# easyeda.net
KiCad netlist of a schematic drawn in EasyEDA
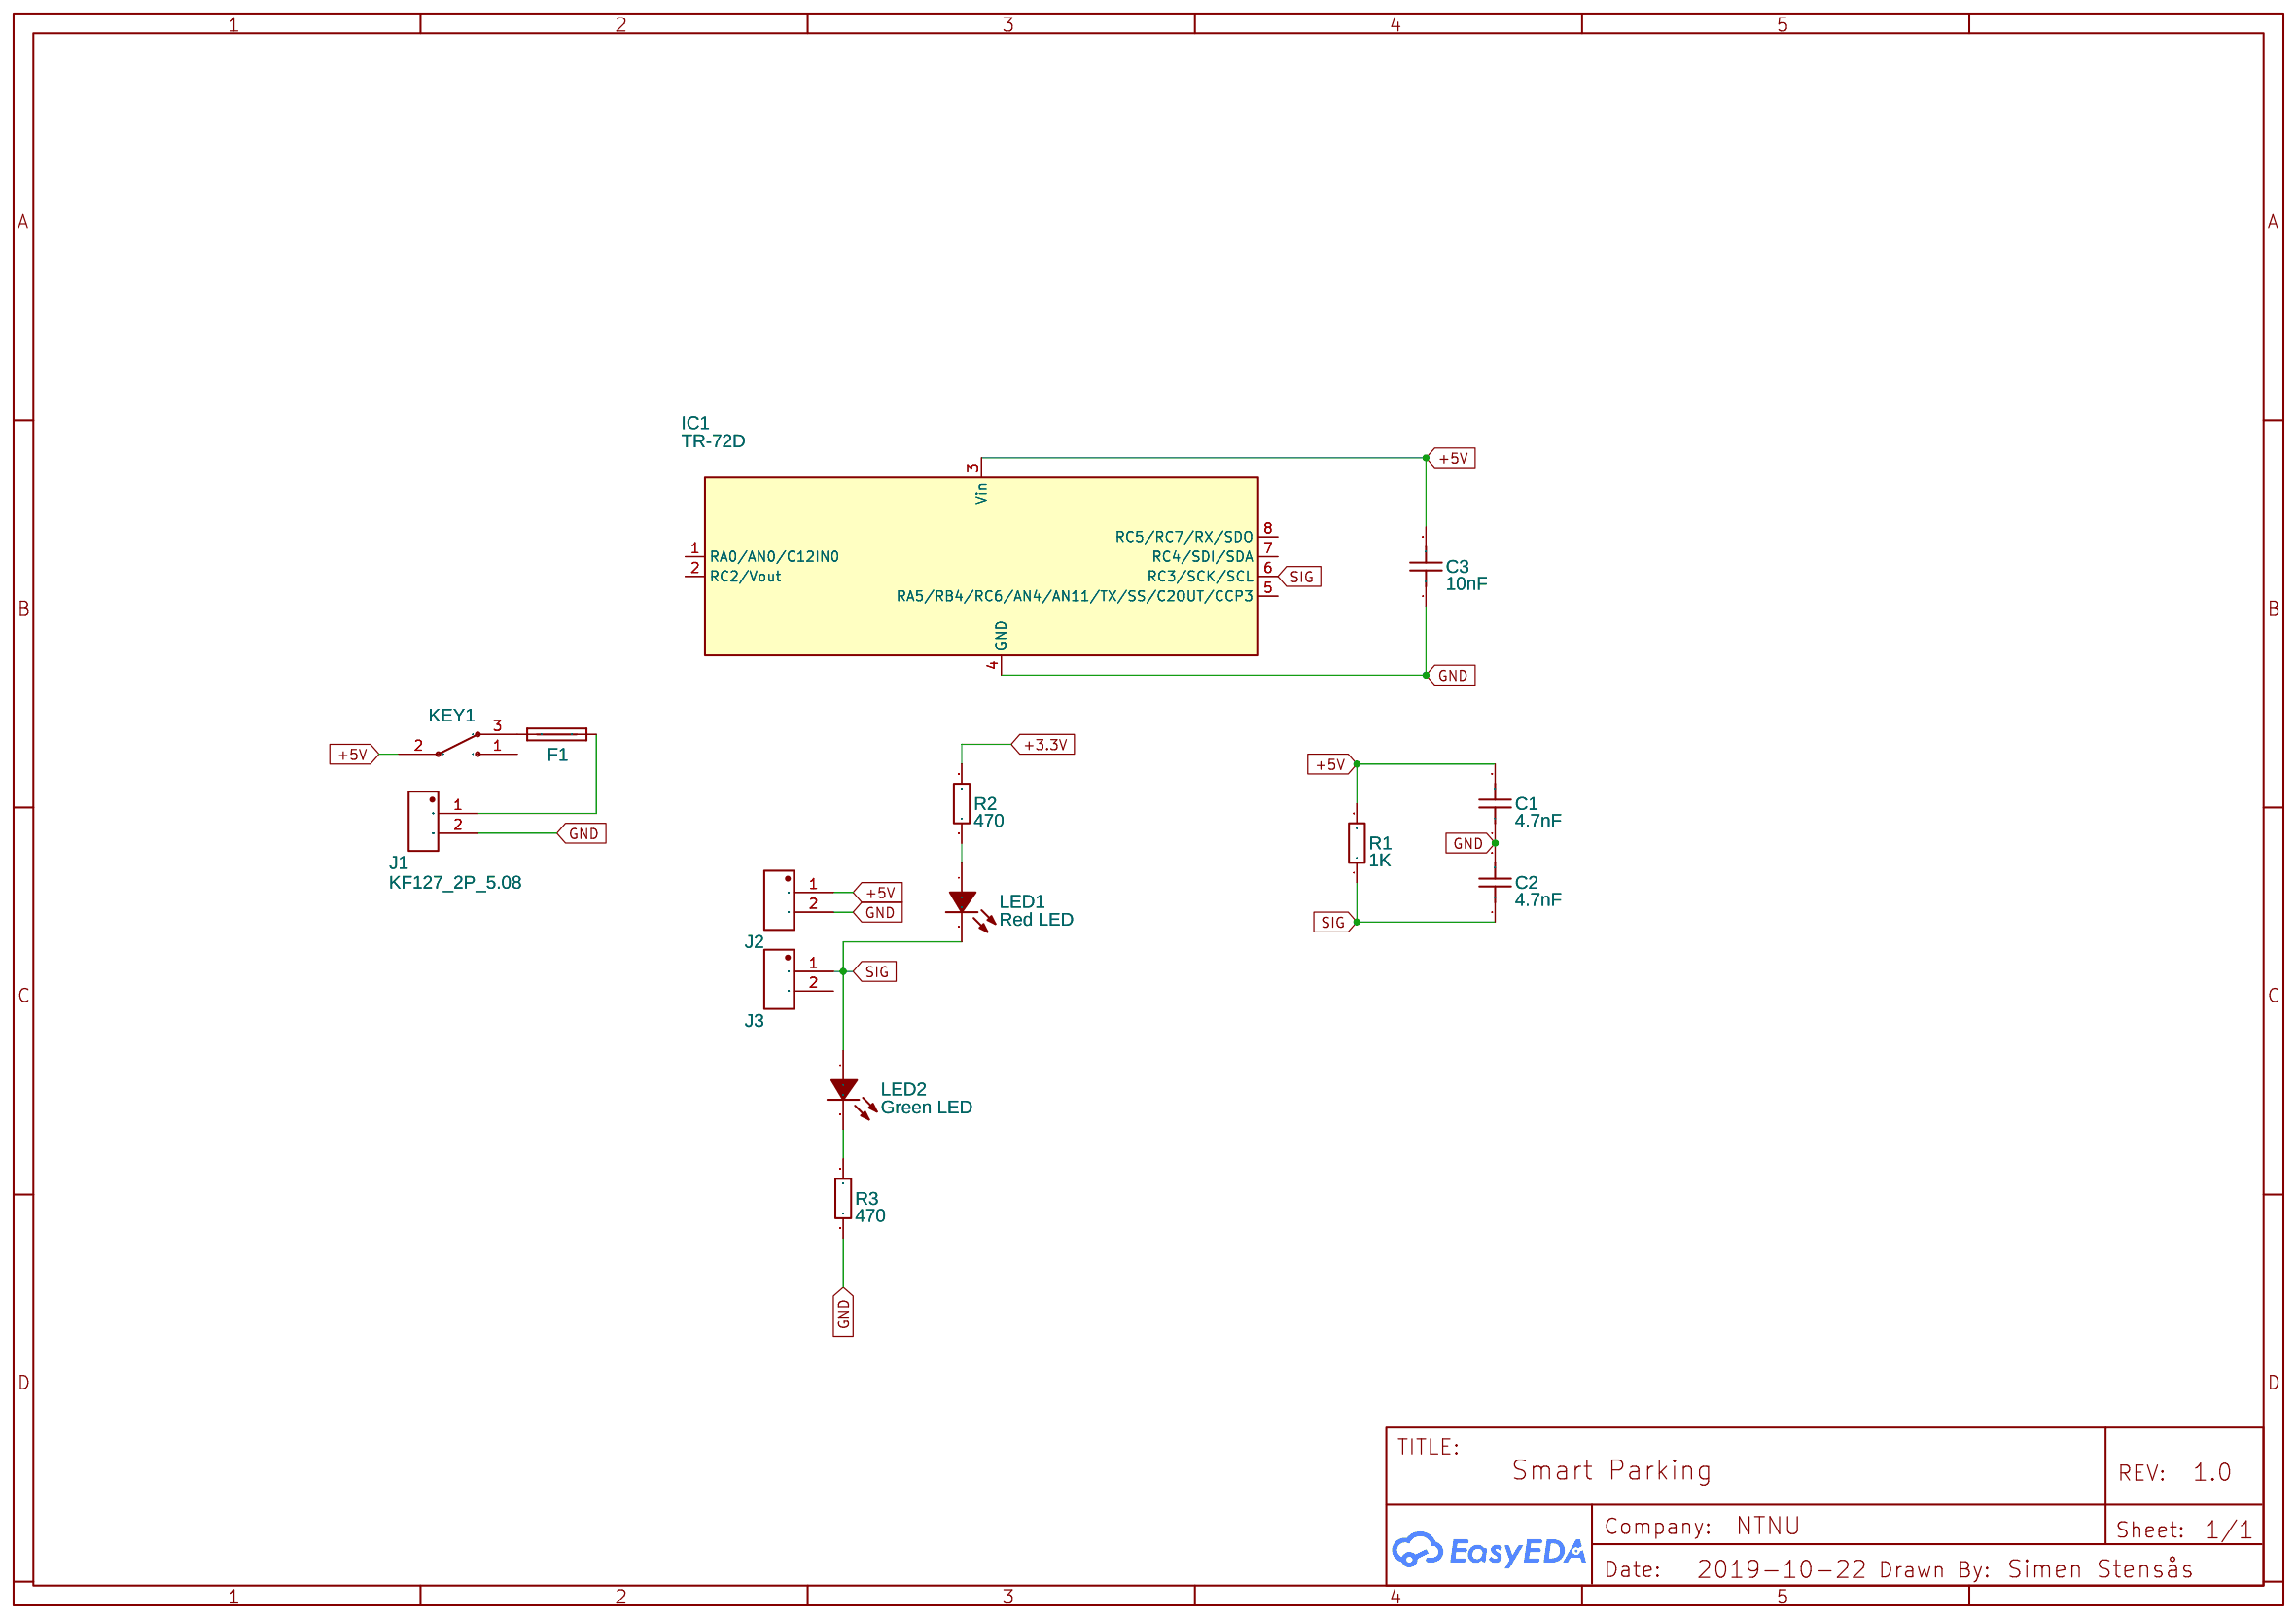
[diagram p0: Smart Parking]
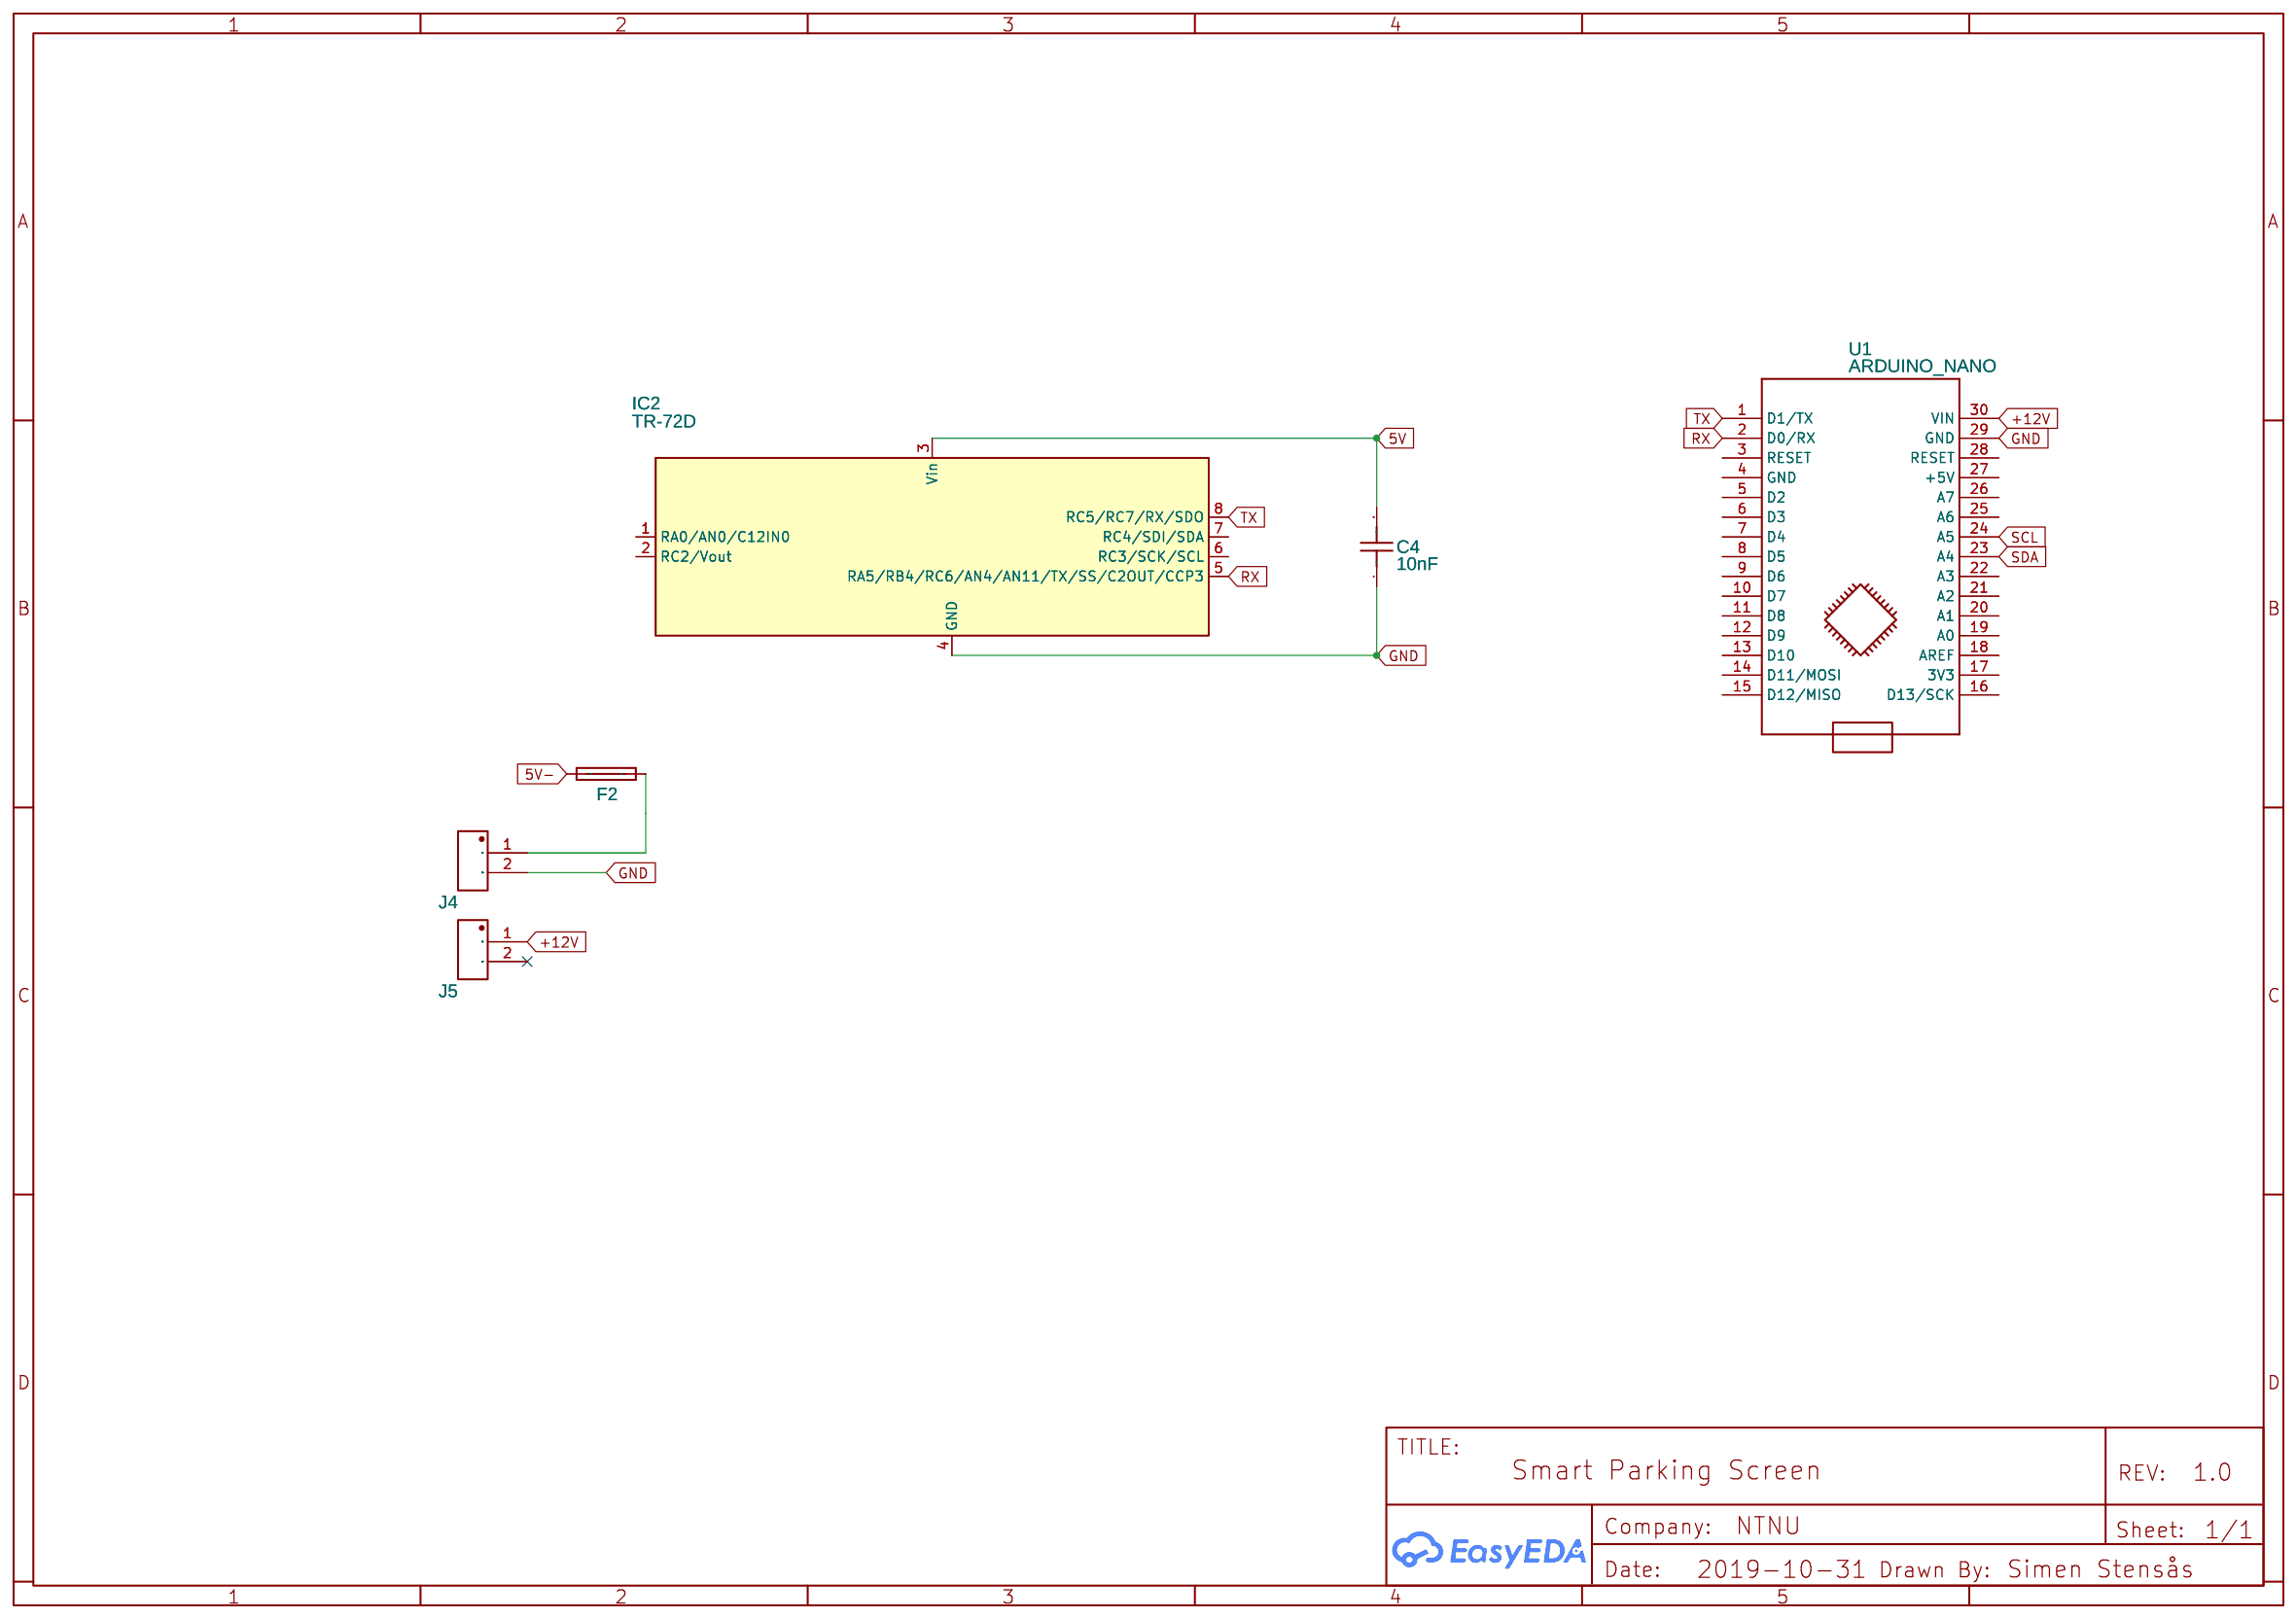
[diagram p1: Smart Parking Screen]

(export (version "E")
  (design (tool "Eeschema 10.0.6"))
  (components
    (comp (ref "C1")
      (value "4.7nF")
      (fields
        (field (name "BOM_Manufacturer Part") "0805B472K201")
        (field (name "BOM_Supplier Part") "C77474")
      )
      (libsource (lib "") (part "0805B472K201"))
    )
    (comp (ref "C2")
      (value "4.7nF")
      (fields
        (field (name "BOM_Manufacturer Part") "0805B472K201")
        (field (name "BOM_Supplier Part") "C77474")
      )
      (libsource (lib "") (part "0805B472K201"))
    )
    (comp (ref "C3")
      (value "10nF")
      (fields
        (field (name "BOM_Manufacturer Part") "0603B103K500AT")
        (field (name "BOM_Supplier Part") "C327421")
      )
      (libsource (lib "") (part "0603B103K500AT"))
    )
    (comp (ref "F1")
      (value "NO")
      (fields
        (field (name "BOM_Manufacturer Part") "3403.0015.11")
        (field (name "BOM_Supplier Part") "693-3403.0015.11")
      )
      (libsource (lib "") (part "Unknown_280_355"))
    )
    (comp (ref "IC1") (value "TR-72D") (libsource (lib "") (part "Unknown_350_275")))
    (comp (ref "J1")
      (value "KF127_2P_5.08")
      (fields (field (name "BOM_Manufacturer Part") "KF127L-5.08"))
      (libsource (lib "") (part "Unknown_220_410"))
    )
    (comp (ref "J2")
      (value "KF127_2P_5.08")
      (fields (field (name "BOM_Manufacturer Part") "KF127L-5.08"))
      (libsource (lib "") (part "Unknown_400_450"))
    )
    (comp (ref "J3")
      (value "KF127_2P_5.08")
      (fields (field (name "BOM_Manufacturer Part") "KF127L-5.08"))
      (libsource (lib "") (part "Unknown_400_490"))
    )
    (comp (ref "KEY1")
      (value "MSK-11027 Toggle Switches")
      (fields (field (name "BOM_Supplier Part") "C21381"))
      (libsource (lib "") (part "Unknown_225_365"))
    )
    (comp (ref "LED1")
      (value "Red LED")
      (fields
        (field (name "BOM_Manufacturer Part") "3528 Red LED")
        (field (name "BOM_Supplier Part") "C2305")
      )
      (libsource (lib "") (part "Unknown_485_450"))
    )
    (comp (ref "LED2")
      (value "Green LED")
      (fields
        (field (name "BOM_Manufacturer Part") "3528 Red LED")
        (field (name "BOM_Supplier Part") "C2305")
      )
      (libsource (lib "") (part "Unknown_425_545"))
    )
    (comp (ref "R1")
      (value "1K")
      (fields
        (field (name "BOM_Manufacturer Part") "CR0805J80102G")
        (field (name "BOM_Supplier Part") "C101925")
      )
      (libsource (lib "") (part "CR0805J80102G"))
    )
    (comp (ref "R2")
      (value "470")
      (fields
        (field (name "BOM_Manufacturer Part") "CR0805J80102G")
        (field (name "BOM_Supplier Part") "C101925")
      )
      (libsource (lib "") (part "CR0805J80102G"))
    )
    (comp (ref "R3")
      (value "470")
      (fields
        (field (name "BOM_Manufacturer Part") "CR0805J80102G")
        (field (name "BOM_Supplier Part") "C101925")
      )
      (libsource (lib "") (part "CR0805J80102G"))
    )
    (comp (ref "C4")
      (value "10nF")
      (fields
        (field (name "BOM_Manufacturer Part") "0603B103K500AT")
        (field (name "BOM_Supplier Part") "C327421")
      )
      (libsource (lib "") (part "0603B103K500AT"))
    )
    (comp (ref "F2")
      (value "NO")
      (fields
        (field (name "BOM_Manufacturer Part") "3403.0015.11")
        (field (name "BOM_Supplier Part") "693-3403.0015.11")
      )
      (libsource (lib "") (part "Unknown_305_375"))
    )
    (comp (ref "IC2") (value "TR-72D") (libsource (lib "") (part "Unknown_325_265")))
    (comp (ref "J4")
      (value "KF127_2P_5.08")
      (fields (field (name "BOM_Manufacturer Part") "KF127L-5.08"))
      (libsource (lib "") (part "Unknown_245_430"))
    )
    (comp (ref "J5")
      (value "KF127_2P_5.08")
      (fields (field (name "BOM_Manufacturer Part") "KF127L-5.08"))
      (libsource (lib "") (part "Unknown_245_475"))
    )
    (comp (ref "U1") (value "ARDUINO_NANO") (libsource (lib "") (part "Unknown_935_280")))
  )
  (nets
    (net (code "1") (name "+3.3V") (class "Default")
      (node (ref "R2") (pin "2") (pinfunction "2_2") (pintype "unspecified"))
    )
    (net (code "2") (name "+5V") (class "Default")
      (node (ref "C1") (pin "2") (pinfunction "2_2") (pintype "unspecified"))
      (node (ref "C3") (pin "2") (pinfunction "2_2") (pintype "unspecified"))
      (node (ref "IC1") (pin "3") (pinfunction "Vin_3") (pintype "bidirectional"))
      (node (ref "J2") (pin "1") (pinfunction "PIN1_1") (pintype "unspecified"))
      (node (ref "KEY1") (pin "2") (pinfunction "2_2") (pintype "unspecified"))
      (node (ref "R1") (pin "2") (pinfunction "2_2") (pintype "unspecified"))
    )
    (net (code "3") (name "+12V") (class "Default")
      (node (ref "J5") (pin "1") (pinfunction "PIN1_1") (pintype "unspecified"))
      (node (ref "U1") (pin "30") (pinfunction "VIN_30") (pintype "unspecified"))
    )
    (net (code "4") (name "5V") (class "Default")
      (node (ref "C4") (pin "2") (pinfunction "2_2") (pintype "unspecified"))
      (node (ref "IC2") (pin "3") (pinfunction "Vin_3") (pintype "bidirectional"))
    )
    (net (code "5") (name "5V-") (class "Default")
      (node (ref "F2") (pin "1") (pinfunction "1_1") (pintype "bidirectional"))
    )
    (net (code "6") (name "GND") (class "Default")
      (node (ref "C1") (pin "1") (pinfunction "1_1") (pintype "unspecified"))
      (node (ref "C2") (pin "2") (pinfunction "2_2") (pintype "unspecified"))
      (node (ref "C3") (pin "1") (pinfunction "1_1") (pintype "unspecified"))
      (node (ref "C4") (pin "1") (pinfunction "1_1") (pintype "unspecified"))
      (node (ref "IC1") (pin "4") (pinfunction "GND_4") (pintype "bidirectional"))
      (node (ref "IC2") (pin "4") (pinfunction "GND_4") (pintype "bidirectional"))
      (node (ref "J1") (pin "2") (pinfunction "PIN2_2") (pintype "unspecified"))
      (node (ref "J2") (pin "2") (pinfunction "PIN2_2") (pintype "unspecified"))
      (node (ref "J4") (pin "2") (pinfunction "PIN2_2") (pintype "unspecified"))
      (node (ref "R3") (pin "1") (pinfunction "1_1") (pintype "unspecified"))
      (node (ref "U1") (pin "29") (pinfunction "GND_29") (pintype "unspecified"))
    )
    (net (code "7") (name "Net-(F1-Pad1)") (class "Default")
      (node (ref "F1") (pin "1") (pinfunction "1_1") (pintype "bidirectional"))
      (node (ref "KEY1") (pin "3") (pinfunction "3_3") (pintype "unspecified"))
    )
    (net (code "8") (name "Net-(J1-PIN1)") (class "Default")
      (node (ref "F1") (pin "2") (pinfunction "2_2") (pintype "bidirectional"))
      (node (ref "J1") (pin "1") (pinfunction "PIN1_1") (pintype "unspecified"))
    )
    (net (code "9") (name "Net-(J4-PIN1)") (class "Default")
      (node (ref "F2") (pin "2") (pinfunction "2_2") (pintype "bidirectional"))
      (node (ref "J4") (pin "1") (pinfunction "PIN1_1") (pintype "unspecified"))
    )
    (net (code "10") (name "Net-(LED1-A)") (class "Default")
      (node (ref "LED1") (pin "1") (pinfunction "A_1") (pintype "unspecified"))
      (node (ref "R2") (pin "1") (pinfunction "1_1") (pintype "unspecified"))
    )
    (net (code "11") (name "Net-(LED2-K)") (class "Default")
      (node (ref "LED2") (pin "2") (pinfunction "K_2") (pintype "unspecified"))
      (node (ref "R3") (pin "2") (pinfunction "2_2") (pintype "unspecified"))
    )
    (net (code "12") (name "RX") (class "Default")
      (node (ref "IC2") (pin "5") (pinfunction "RA5/RB4/RC6/AN4/AN11/TX/SS/C2OUT/CCP3_5") (pintype "bidirectional"))
      (node (ref "U1") (pin "2") (pinfunction "D0/RX_2") (pintype "unspecified"))
    )
    (net (code "13") (name "SCL") (class "Default")
      (node (ref "U1") (pin "24") (pinfunction "A5_24") (pintype "unspecified"))
    )
    (net (code "14") (name "SDA") (class "Default")
      (node (ref "U1") (pin "23") (pinfunction "A4_23") (pintype "unspecified"))
    )
    (net (code "15") (name "SIG") (class "Default")
      (node (ref "C2") (pin "1") (pinfunction "1_1") (pintype "unspecified"))
      (node (ref "IC1") (pin "6") (pinfunction "RC3/SCK/SCL_6") (pintype "bidirectional"))
      (node (ref "J3") (pin "1") (pinfunction "PIN1_1") (pintype "unspecified"))
      (node (ref "LED1") (pin "2") (pinfunction "K_2") (pintype "unspecified"))
      (node (ref "LED2") (pin "1") (pinfunction "A_1") (pintype "unspecified"))
      (node (ref "R1") (pin "1") (pinfunction "1_1") (pintype "unspecified"))
    )
    (net (code "16") (name "TX") (class "Default")
      (node (ref "IC2") (pin "8") (pinfunction "RC5/RC7/RX/SDO_8") (pintype "bidirectional"))
      (node (ref "U1") (pin "1") (pinfunction "D1/TX_1") (pintype "unspecified"))
    )
    (net (code "17") (name "unconnected-(IC1-RA0{slash}AN0{slash}C12IN0-Pad1)") (class "Default")
      (node (ref "IC1") (pin "1") (pinfunction "RA0/AN0/C12IN0_1") (pintype "bidirectional"))
    )
    (net (code "18") (name "unconnected-(IC1-RA5{slash}RB4{slash}RC6{slash}AN4{slash}AN11{slash}TX{slash}SS{slash}C2OUT{slash}CCP3-Pad5)") (class "Default")
      (node (ref "IC1") (pin "5") (pinfunction "RA5/RB4/RC6/AN4/AN11/TX/SS/C2OUT/CCP3_5") (pintype "bidirectional"))
    )
    (net (code "19") (name "unconnected-(IC1-RC2{slash}Vout-Pad2)") (class "Default")
      (node (ref "IC1") (pin "2") (pinfunction "RC2/Vout_2") (pintype "bidirectional"))
    )
    (net (code "20") (name "unconnected-(IC1-RC4{slash}SDI{slash}SDA-Pad7)") (class "Default")
      (node (ref "IC1") (pin "7") (pinfunction "RC4/SDI/SDA_7") (pintype "bidirectional"))
    )
    (net (code "21") (name "unconnected-(IC1-RC5{slash}RC7{slash}RX{slash}SDO-Pad8)") (class "Default")
      (node (ref "IC1") (pin "8") (pinfunction "RC5/RC7/RX/SDO_8") (pintype "bidirectional"))
    )
    (net (code "22") (name "unconnected-(IC2-RA0{slash}AN0{slash}C12IN0-Pad1)") (class "Default")
      (node (ref "IC2") (pin "1") (pinfunction "RA0/AN0/C12IN0_1") (pintype "bidirectional"))
    )
    (net (code "23") (name "unconnected-(IC2-RC2{slash}Vout-Pad2)") (class "Default")
      (node (ref "IC2") (pin "2") (pinfunction "RC2/Vout_2") (pintype "bidirectional"))
    )
    (net (code "24") (name "unconnected-(IC2-RC3{slash}SCK{slash}SCL-Pad6)") (class "Default")
      (node (ref "IC2") (pin "6") (pinfunction "RC3/SCK/SCL_6") (pintype "bidirectional"))
    )
    (net (code "25") (name "unconnected-(IC2-RC4{slash}SDI{slash}SDA-Pad7)") (class "Default")
      (node (ref "IC2") (pin "7") (pinfunction "RC4/SDI/SDA_7") (pintype "bidirectional"))
    )
    (net (code "26") (name "unconnected-(J3-PIN2-Pad2)") (class "Default")
      (node (ref "J3") (pin "2") (pinfunction "PIN2_2") (pintype "unspecified"))
    )
    (net (code "27") (name "unconnected-(J5-PIN2-Pad2)") (class "Default")
      (node (ref "J5") (pin "2") (pinfunction "PIN2_2") (pintype "unspecified+no_connect"))
    )
    (net (code "28") (name "unconnected-(KEY1-Pad1)") (class "Default")
      (node (ref "KEY1") (pin "1") (pinfunction "1_1") (pintype "unspecified"))
    )
    (net (code "29") (name "unconnected-(U1-+5V-Pad27)") (class "Default")
      (node (ref "U1") (pin "27") (pinfunction "+5V_27") (pintype "unspecified"))
    )
    (net (code "30") (name "unconnected-(U1-3V3-Pad17)") (class "Default")
      (node (ref "U1") (pin "17") (pinfunction "3V3_17") (pintype "unspecified"))
    )
    (net (code "31") (name "unconnected-(U1-A0-Pad19)") (class "Default")
      (node (ref "U1") (pin "19") (pinfunction "A0_19") (pintype "unspecified"))
    )
    (net (code "32") (name "unconnected-(U1-A1-Pad20)") (class "Default")
      (node (ref "U1") (pin "20") (pinfunction "A1_20") (pintype "unspecified"))
    )
    (net (code "33") (name "unconnected-(U1-A2-Pad21)") (class "Default")
      (node (ref "U1") (pin "21") (pinfunction "A2_21") (pintype "unspecified"))
    )
    (net (code "34") (name "unconnected-(U1-A3-Pad22)") (class "Default")
      (node (ref "U1") (pin "22") (pinfunction "A3_22") (pintype "unspecified"))
    )
    (net (code "35") (name "unconnected-(U1-A6-Pad25)") (class "Default")
      (node (ref "U1") (pin "25") (pinfunction "A6_25") (pintype "unspecified"))
    )
    (net (code "36") (name "unconnected-(U1-A7-Pad26)") (class "Default")
      (node (ref "U1") (pin "26") (pinfunction "A7_26") (pintype "unspecified"))
    )
    (net (code "37") (name "unconnected-(U1-AREF-Pad18)") (class "Default")
      (node (ref "U1") (pin "18") (pinfunction "AREF_18") (pintype "unspecified"))
    )
    (net (code "38") (name "unconnected-(U1-D2-Pad5)") (class "Default")
      (node (ref "U1") (pin "5") (pinfunction "D2_5") (pintype "unspecified"))
    )
    (net (code "39") (name "unconnected-(U1-D3-Pad6)") (class "Default")
      (node (ref "U1") (pin "6") (pinfunction "D3_6") (pintype "unspecified"))
    )
    (net (code "40") (name "unconnected-(U1-D4-Pad7)") (class "Default")
      (node (ref "U1") (pin "7") (pinfunction "D4_7") (pintype "unspecified"))
    )
    (net (code "41") (name "unconnected-(U1-D5-Pad8)") (class "Default")
      (node (ref "U1") (pin "8") (pinfunction "D5_8") (pintype "unspecified"))
    )
    (net (code "42") (name "unconnected-(U1-D6-Pad9)") (class "Default")
      (node (ref "U1") (pin "9") (pinfunction "D6_9") (pintype "unspecified"))
    )
    (net (code "43") (name "unconnected-(U1-D7-Pad10)") (class "Default")
      (node (ref "U1") (pin "10") (pinfunction "D7_10") (pintype "unspecified"))
    )
    (net (code "44") (name "unconnected-(U1-D8-Pad11)") (class "Default")
      (node (ref "U1") (pin "11") (pinfunction "D8_11") (pintype "unspecified"))
    )
    (net (code "45") (name "unconnected-(U1-D9-Pad12)") (class "Default")
      (node (ref "U1") (pin "12") (pinfunction "D9_12") (pintype "unspecified"))
    )
    (net (code "46") (name "unconnected-(U1-D10-Pad13)") (class "Default")
      (node (ref "U1") (pin "13") (pinfunction "D10_13") (pintype "unspecified"))
    )
    (net (code "47") (name "unconnected-(U1-D11{slash}MOSI-Pad14)") (class "Default")
      (node (ref "U1") (pin "14") (pinfunction "D11/MOSI_14") (pintype "unspecified"))
    )
    (net (code "48") (name "unconnected-(U1-D12{slash}MISO-Pad15)") (class "Default")
      (node (ref "U1") (pin "15") (pinfunction "D12/MISO_15") (pintype "unspecified"))
    )
    (net (code "49") (name "unconnected-(U1-D13{slash}SCK-Pad16)") (class "Default")
      (node (ref "U1") (pin "16") (pinfunction "D13/SCK_16") (pintype "unspecified"))
    )
    (net (code "50") (name "unconnected-(U1-GND-Pad4)") (class "Default")
      (node (ref "U1") (pin "4") (pinfunction "GND_4") (pintype "unspecified"))
    )
    (net (code "51") (name "unconnected-(U1-RESET-Pad3)") (class "Default")
      (node (ref "U1") (pin "3") (pinfunction "RESET_3") (pintype "unspecified"))
    )
    (net (code "52") (name "unconnected-(U1-RESET-Pad28)") (class "Default")
      (node (ref "U1") (pin "28") (pinfunction "RESET_28") (pintype "unspecified"))
    )
  )
)
